# FPGADecoupling.net
KiCad netlist of a schematic drawn in Altium Designer
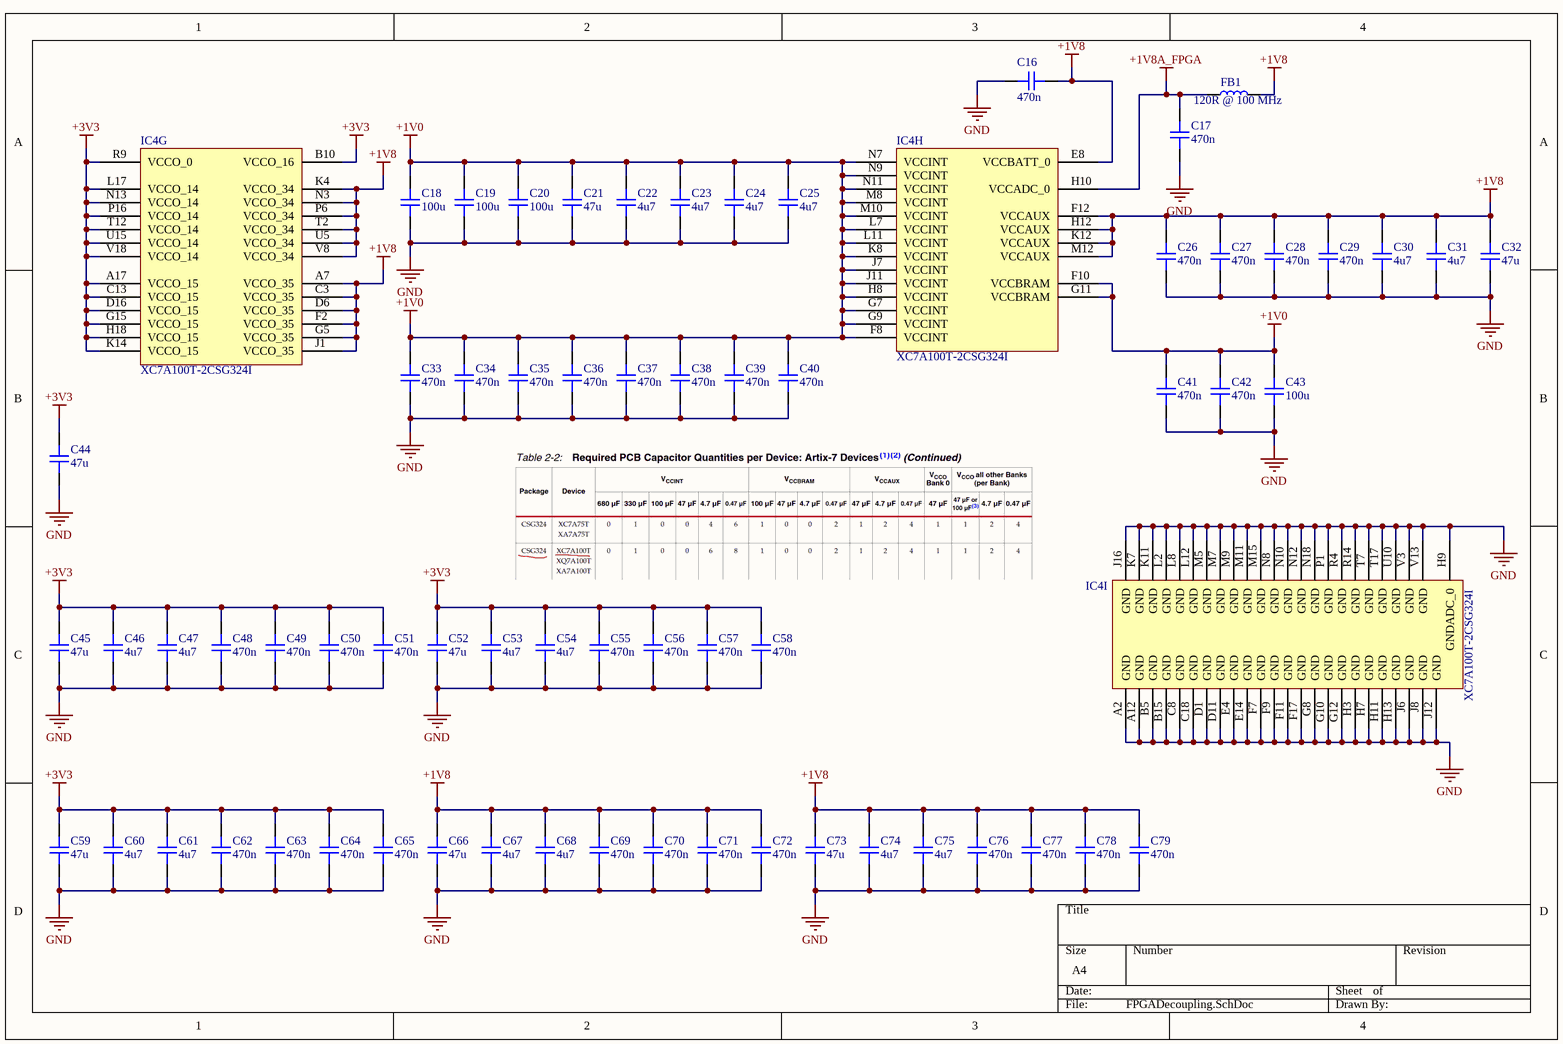
[diagram p0: FPGADecoupling.SchDoc]

(export (version "E")
  (design (tool "Eeschema 10.0.6"))
  (components
    (comp (ref "C16")
      (value "470n")
      (footprint "CAP_0201")
      (description "Capacitor SMD 0201")
      (libsource (lib "Schematic-Lib-PhilsLab") (part "CAP_0201"))
    )
    (comp (ref "C17")
      (value "470n")
      (footprint "CAP_0201")
      (description "Capacitor SMD 0201")
      (libsource (lib "Schematic-Lib-PhilsLab") (part "CAP_0201"))
    )
    (comp (ref "C18")
      (value "100u")
      (footprint "CAP_0805")
      (description "Capacitor SMD 0805")
      (libsource (lib "Schematic-Lib-PhilsLab") (part "CAP_0805"))
    )
    (comp (ref "C19")
      (value "100u")
      (footprint "CAP_0805")
      (description "Capacitor SMD 0805")
      (libsource (lib "Schematic-Lib-PhilsLab") (part "CAP_0805"))
    )
    (comp (ref "C20")
      (value "100u")
      (footprint "CAP_0805")
      (description "Capacitor SMD 0805")
      (libsource (lib "Schematic-Lib-PhilsLab") (part "CAP_0805"))
    )
    (comp (ref "C21")
      (value "47u")
      (footprint "CAP_0603")
      (description "Capacitor SMD 0603")
      (libsource (lib "Schematic-Lib-PhilsLab") (part "CAP_0603"))
    )
    (comp (ref "C22")
      (value "4u7")
      (footprint "CAP_0402")
      (description "Capacitor SMD 0402")
      (libsource (lib "Schematic-Lib-PhilsLab") (part "CAP_0402"))
    )
    (comp (ref "C23")
      (value "4u7")
      (footprint "CAP_0402")
      (description "Capacitor SMD 0402")
      (libsource (lib "Schematic-Lib-PhilsLab") (part "CAP_0402"))
    )
    (comp (ref "C24")
      (value "4u7")
      (footprint "CAP_0402")
      (description "Capacitor SMD 0402")
      (libsource (lib "Schematic-Lib-PhilsLab") (part "CAP_0402"))
    )
    (comp (ref "C25")
      (value "4u7")
      (footprint "CAP_0402")
      (description "Capacitor SMD 0402")
      (libsource (lib "Schematic-Lib-PhilsLab") (part "CAP_0402"))
    )
    (comp (ref "C26")
      (value "470n")
      (footprint "CAP_0201")
      (description "Capacitor SMD 0201")
      (libsource (lib "Schematic-Lib-PhilsLab") (part "CAP_0201"))
    )
    (comp (ref "C27")
      (value "470n")
      (footprint "CAP_0201")
      (description "Capacitor SMD 0201")
      (libsource (lib "Schematic-Lib-PhilsLab") (part "CAP_0201"))
    )
    (comp (ref "C28")
      (value "470n")
      (footprint "CAP_0201")
      (description "Capacitor SMD 0201")
      (libsource (lib "Schematic-Lib-PhilsLab") (part "CAP_0201"))
    )
    (comp (ref "C29")
      (value "470n")
      (footprint "CAP_0201")
      (description "Capacitor SMD 0201")
      (libsource (lib "Schematic-Lib-PhilsLab") (part "CAP_0201"))
    )
    (comp (ref "C30")
      (value "4u7")
      (footprint "CAP_0402")
      (description "Capacitor SMD 0402")
      (libsource (lib "Schematic-Lib-PhilsLab") (part "CAP_0402"))
    )
    (comp (ref "C31")
      (value "4u7")
      (footprint "CAP_0402")
      (description "Capacitor SMD 0402")
      (libsource (lib "Schematic-Lib-PhilsLab") (part "CAP_0402"))
    )
    (comp (ref "C32")
      (value "47u")
      (footprint "CAP_0603")
      (description "Capacitor SMD 0603")
      (libsource (lib "Schematic-Lib-PhilsLab") (part "CAP_0603"))
    )
    (comp (ref "C33")
      (value "470n")
      (footprint "CAP_0201")
      (description "Capacitor SMD 0201")
      (libsource (lib "Schematic-Lib-PhilsLab") (part "CAP_0201"))
    )
    (comp (ref "C34")
      (value "470n")
      (footprint "CAP_0201")
      (description "Capacitor SMD 0201")
      (libsource (lib "Schematic-Lib-PhilsLab") (part "CAP_0201"))
    )
    (comp (ref "C35")
      (value "470n")
      (footprint "CAP_0201")
      (description "Capacitor SMD 0201")
      (libsource (lib "Schematic-Lib-PhilsLab") (part "CAP_0201"))
    )
    (comp (ref "C36")
      (value "470n")
      (footprint "CAP_0201")
      (description "Capacitor SMD 0201")
      (libsource (lib "Schematic-Lib-PhilsLab") (part "CAP_0201"))
    )
    (comp (ref "C37")
      (value "470n")
      (footprint "CAP_0201")
      (description "Capacitor SMD 0201")
      (libsource (lib "Schematic-Lib-PhilsLab") (part "CAP_0201"))
    )
    (comp (ref "C38")
      (value "470n")
      (footprint "CAP_0201")
      (description "Capacitor SMD 0201")
      (libsource (lib "Schematic-Lib-PhilsLab") (part "CAP_0201"))
    )
    (comp (ref "C39")
      (value "470n")
      (footprint "CAP_0201")
      (description "Capacitor SMD 0201")
      (libsource (lib "Schematic-Lib-PhilsLab") (part "CAP_0201"))
    )
    (comp (ref "C40")
      (value "470n")
      (footprint "CAP_0201")
      (description "Capacitor SMD 0201")
      (libsource (lib "Schematic-Lib-PhilsLab") (part "CAP_0201"))
    )
    (comp (ref "C41")
      (value "470n")
      (footprint "CAP_0201")
      (description "Capacitor SMD 0201")
      (libsource (lib "Schematic-Lib-PhilsLab") (part "CAP_0201"))
    )
    (comp (ref "C42")
      (value "470n")
      (footprint "CAP_0201")
      (description "Capacitor SMD 0201")
      (libsource (lib "Schematic-Lib-PhilsLab") (part "CAP_0201"))
    )
    (comp (ref "C43")
      (value "100u")
      (footprint "CAP_0805")
      (description "Capacitor SMD 0805")
      (libsource (lib "Schematic-Lib-PhilsLab") (part "CAP_0805"))
    )
    (comp (ref "C44")
      (value "47u")
      (footprint "CAP_0603")
      (description "Capacitor SMD 0603")
      (libsource (lib "Schematic-Lib-PhilsLab") (part "CAP_0603"))
    )
    (comp (ref "C45")
      (value "47u")
      (footprint "CAP_0603")
      (description "Capacitor SMD 0603")
      (libsource (lib "Schematic-Lib-PhilsLab") (part "CAP_0603"))
    )
    (comp (ref "C46")
      (value "4u7")
      (footprint "CAP_0402")
      (description "Capacitor SMD 0402")
      (libsource (lib "Schematic-Lib-PhilsLab") (part "CAP_0402"))
    )
    (comp (ref "C47")
      (value "4u7")
      (footprint "CAP_0402")
      (description "Capacitor SMD 0402")
      (libsource (lib "Schematic-Lib-PhilsLab") (part "CAP_0402"))
    )
    (comp (ref "C48")
      (value "470n")
      (footprint "CAP_0201")
      (description "Capacitor SMD 0201")
      (libsource (lib "Schematic-Lib-PhilsLab") (part "CAP_0201"))
    )
    (comp (ref "C49")
      (value "470n")
      (footprint "CAP_0201")
      (description "Capacitor SMD 0201")
      (libsource (lib "Schematic-Lib-PhilsLab") (part "CAP_0201"))
    )
    (comp (ref "C50")
      (value "470n")
      (footprint "CAP_0201")
      (description "Capacitor SMD 0201")
      (libsource (lib "Schematic-Lib-PhilsLab") (part "CAP_0201"))
    )
    (comp (ref "C51")
      (value "470n")
      (footprint "CAP_0201")
      (description "Capacitor SMD 0201")
      (libsource (lib "Schematic-Lib-PhilsLab") (part "CAP_0201"))
    )
    (comp (ref "C52")
      (value "47u")
      (footprint "CAP_0603")
      (description "Capacitor SMD 0603")
      (libsource (lib "Schematic-Lib-PhilsLab") (part "CAP_0603"))
    )
    (comp (ref "C53")
      (value "4u7")
      (footprint "CAP_0402")
      (description "Capacitor SMD 0402")
      (libsource (lib "Schematic-Lib-PhilsLab") (part "CAP_0402"))
    )
    (comp (ref "C54")
      (value "4u7")
      (footprint "CAP_0402")
      (description "Capacitor SMD 0402")
      (libsource (lib "Schematic-Lib-PhilsLab") (part "CAP_0402"))
    )
    (comp (ref "C55")
      (value "470n")
      (footprint "CAP_0201")
      (description "Capacitor SMD 0201")
      (libsource (lib "Schematic-Lib-PhilsLab") (part "CAP_0201"))
    )
    (comp (ref "C56")
      (value "470n")
      (footprint "CAP_0201")
      (description "Capacitor SMD 0201")
      (libsource (lib "Schematic-Lib-PhilsLab") (part "CAP_0201"))
    )
    (comp (ref "C57")
      (value "470n")
      (footprint "CAP_0201")
      (description "Capacitor SMD 0201")
      (libsource (lib "Schematic-Lib-PhilsLab") (part "CAP_0201"))
    )
    (comp (ref "C58")
      (value "470n")
      (footprint "CAP_0201")
      (description "Capacitor SMD 0201")
      (libsource (lib "Schematic-Lib-PhilsLab") (part "CAP_0201"))
    )
    (comp (ref "C59")
      (value "47u")
      (footprint "CAP_0603")
      (description "Capacitor SMD 0603")
      (libsource (lib "Schematic-Lib-PhilsLab") (part "CAP_0603"))
    )
    (comp (ref "C60")
      (value "4u7")
      (footprint "CAP_0402")
      (description "Capacitor SMD 0402")
      (libsource (lib "Schematic-Lib-PhilsLab") (part "CAP_0402"))
    )
    (comp (ref "C61")
      (value "4u7")
      (footprint "CAP_0402")
      (description "Capacitor SMD 0402")
      (libsource (lib "Schematic-Lib-PhilsLab") (part "CAP_0402"))
    )
    (comp (ref "C62")
      (value "470n")
      (footprint "CAP_0201")
      (description "Capacitor SMD 0201")
      (libsource (lib "Schematic-Lib-PhilsLab") (part "CAP_0201"))
    )
    (comp (ref "C63")
      (value "470n")
      (footprint "CAP_0201")
      (description "Capacitor SMD 0201")
      (libsource (lib "Schematic-Lib-PhilsLab") (part "CAP_0201"))
    )
    (comp (ref "C64")
      (value "470n")
      (footprint "CAP_0201")
      (description "Capacitor SMD 0201")
      (libsource (lib "Schematic-Lib-PhilsLab") (part "CAP_0201"))
    )
    (comp (ref "C65")
      (value "470n")
      (footprint "CAP_0201")
      (description "Capacitor SMD 0201")
      (libsource (lib "Schematic-Lib-PhilsLab") (part "CAP_0201"))
    )
    (comp (ref "C66")
      (value "47u")
      (footprint "CAP_0603")
      (description "Capacitor SMD 0603")
      (libsource (lib "Schematic-Lib-PhilsLab") (part "CAP_0603"))
    )
    (comp (ref "C67")
      (value "4u7")
      (footprint "CAP_0402")
      (description "Capacitor SMD 0402")
      (libsource (lib "Schematic-Lib-PhilsLab") (part "CAP_0402"))
    )
    (comp (ref "C68")
      (value "4u7")
      (footprint "CAP_0402")
      (description "Capacitor SMD 0402")
      (libsource (lib "Schematic-Lib-PhilsLab") (part "CAP_0402"))
    )
    (comp (ref "C69")
      (value "470n")
      (footprint "CAP_0201")
      (description "Capacitor SMD 0201")
      (libsource (lib "Schematic-Lib-PhilsLab") (part "CAP_0201"))
    )
    (comp (ref "C70")
      (value "470n")
      (footprint "CAP_0201")
      (description "Capacitor SMD 0201")
      (libsource (lib "Schematic-Lib-PhilsLab") (part "CAP_0201"))
    )
    (comp (ref "C71")
      (value "470n")
      (footprint "CAP_0201")
      (description "Capacitor SMD 0201")
      (libsource (lib "Schematic-Lib-PhilsLab") (part "CAP_0201"))
    )
    (comp (ref "C72")
      (value "470n")
      (footprint "CAP_0201")
      (description "Capacitor SMD 0201")
      (libsource (lib "Schematic-Lib-PhilsLab") (part "CAP_0201"))
    )
    (comp (ref "C73")
      (value "47u")
      (footprint "CAP_0603")
      (description "Capacitor SMD 0603")
      (libsource (lib "Schematic-Lib-PhilsLab") (part "CAP_0603"))
    )
    (comp (ref "C74")
      (value "4u7")
      (footprint "CAP_0402")
      (description "Capacitor SMD 0402")
      (libsource (lib "Schematic-Lib-PhilsLab") (part "CAP_0402"))
    )
    (comp (ref "C75")
      (value "4u7")
      (footprint "CAP_0402")
      (description "Capacitor SMD 0402")
      (libsource (lib "Schematic-Lib-PhilsLab") (part "CAP_0402"))
    )
    (comp (ref "C76")
      (value "470n")
      (footprint "CAP_0201")
      (description "Capacitor SMD 0201")
      (libsource (lib "Schematic-Lib-PhilsLab") (part "CAP_0201"))
    )
    (comp (ref "C77")
      (value "470n")
      (footprint "CAP_0201")
      (description "Capacitor SMD 0201")
      (libsource (lib "Schematic-Lib-PhilsLab") (part "CAP_0201"))
    )
    (comp (ref "C78")
      (value "470n")
      (footprint "CAP_0201")
      (description "Capacitor SMD 0201")
      (libsource (lib "Schematic-Lib-PhilsLab") (part "CAP_0201"))
    )
    (comp (ref "C79")
      (value "470n")
      (footprint "CAP_0201")
      (description "Capacitor SMD 0201")
      (libsource (lib "Schematic-Lib-PhilsLab") (part "CAP_0201"))
    )
    (comp (ref "FB1")
      (value "120R @ 100 MHz")
      (footprint "Footprint-Lib-PhilsLab:IND_0201")
      (description "Inductor SMD 0201")
      (fields
        (field (name "MANUFACTURER_PART_NUMBER") "LQP03HQ56NH02D")
        (field (name "MOUSER PART NUMBER") "81-LQP03HQ56NH02D")
      )
      (libsource (lib "Schematic-Lib-PhilsLab") (part "IND_0201"))
    )
    (comp (ref "IC4")
      (value "XC7A100T-2CSG324I")
      (footprint "CSG324")
      (description "Artix-7 FPGA, 210 User I/Os, 0 GTP, 324-Ball BGA, Speed Grade 2, Industrial Grade, Pb-Free")
      (fields (field (name "GENERIC PART NUMBER") "XC7A100T") (field (name "MANUFACTURER") "Xilinx"))
      (libsource (lib "Schematic-Lib-PhilsLab") (part "XC7A100T-2CSG324I"))
    )
  )
  (nets
    (net (code "1") (name "+1V0") (class "Default")
      (node (ref "C18") (pin "2") (pinfunction "2_2") (pintype "passive"))
      (node (ref "C19") (pin "2") (pinfunction "2_2") (pintype "passive"))
      (node (ref "C20") (pin "2") (pinfunction "2_2") (pintype "passive"))
      (node (ref "C21") (pin "2") (pinfunction "2_2") (pintype "passive"))
      (node (ref "C22") (pin "2") (pinfunction "2_2") (pintype "passive"))
      (node (ref "C23") (pin "2") (pinfunction "2_2") (pintype "passive"))
      (node (ref "C24") (pin "2") (pinfunction "2_2") (pintype "passive"))
      (node (ref "C25") (pin "2") (pinfunction "2_2") (pintype "passive"))
      (node (ref "C33") (pin "2") (pinfunction "2_2") (pintype "passive"))
      (node (ref "C34") (pin "2") (pinfunction "2_2") (pintype "passive"))
      (node (ref "C35") (pin "2") (pinfunction "2_2") (pintype "passive"))
      (node (ref "C36") (pin "2") (pinfunction "2_2") (pintype "passive"))
      (node (ref "C37") (pin "2") (pinfunction "2_2") (pintype "passive"))
      (node (ref "C38") (pin "2") (pinfunction "2_2") (pintype "passive"))
      (node (ref "C39") (pin "2") (pinfunction "2_2") (pintype "passive"))
      (node (ref "C40") (pin "2") (pinfunction "2_2") (pintype "passive"))
      (node (ref "C41") (pin "2") (pinfunction "2_2") (pintype "passive"))
      (node (ref "C42") (pin "2") (pinfunction "2_2") (pintype "passive"))
      (node (ref "C43") (pin "2") (pinfunction "2_2") (pintype "passive"))
      (node (ref "IC4") (pin "F10") (pinfunction "VCCBRAM_F10") (pintype "power_in"))
      (node (ref "IC4") (pin "F8") (pinfunction "VCCINT_F8") (pintype "power_in"))
      (node (ref "IC4") (pin "G11") (pinfunction "VCCBRAM_G11") (pintype "power_in"))
      (node (ref "IC4") (pin "G7") (pinfunction "VCCINT_G7") (pintype "power_in"))
      (node (ref "IC4") (pin "G9") (pinfunction "VCCINT_G9") (pintype "power_in"))
      (node (ref "IC4") (pin "H8") (pinfunction "VCCINT_H8") (pintype "power_in"))
      (node (ref "IC4") (pin "J11") (pinfunction "VCCINT_J11") (pintype "power_in"))
      (node (ref "IC4") (pin "J7") (pinfunction "VCCINT_J7") (pintype "power_in"))
      (node (ref "IC4") (pin "K8") (pinfunction "VCCINT_K8") (pintype "power_in"))
      (node (ref "IC4") (pin "L11") (pinfunction "VCCINT_L11") (pintype "power_in"))
      (node (ref "IC4") (pin "L7") (pinfunction "VCCINT_L7") (pintype "power_in"))
      (node (ref "IC4") (pin "M10") (pinfunction "VCCINT_M10") (pintype "power_in"))
      (node (ref "IC4") (pin "M8") (pinfunction "VCCINT_M8") (pintype "power_in"))
      (node (ref "IC4") (pin "N11") (pinfunction "VCCINT_N11") (pintype "power_in"))
      (node (ref "IC4") (pin "N7") (pinfunction "VCCINT_N7") (pintype "power_in"))
      (node (ref "IC4") (pin "N9") (pinfunction "VCCINT_N9") (pintype "power_in"))
    )
    (net (code "2") (name "+1V8") (class "Default")
      (node (ref "C16") (pin "2") (pinfunction "2_2") (pintype "passive"))
      (node (ref "C26") (pin "2") (pinfunction "2_2") (pintype "passive"))
      (node (ref "C27") (pin "2") (pinfunction "2_2") (pintype "passive"))
      (node (ref "C28") (pin "2") (pinfunction "2_2") (pintype "passive"))
      (node (ref "C29") (pin "2") (pinfunction "2_2") (pintype "passive"))
      (node (ref "C30") (pin "2") (pinfunction "2_2") (pintype "passive"))
      (node (ref "C31") (pin "2") (pinfunction "2_2") (pintype "passive"))
      (node (ref "C32") (pin "2") (pinfunction "2_2") (pintype "passive"))
      (node (ref "C66") (pin "2") (pinfunction "2_2") (pintype "passive"))
      (node (ref "C67") (pin "2") (pinfunction "2_2") (pintype "passive"))
      (node (ref "C68") (pin "2") (pinfunction "2_2") (pintype "passive"))
      (node (ref "C69") (pin "2") (pinfunction "2_2") (pintype "passive"))
      (node (ref "C70") (pin "2") (pinfunction "2_2") (pintype "passive"))
      (node (ref "C71") (pin "2") (pinfunction "2_2") (pintype "passive"))
      (node (ref "C72") (pin "2") (pinfunction "2_2") (pintype "passive"))
      (node (ref "C73") (pin "2") (pinfunction "2_2") (pintype "passive"))
      (node (ref "C74") (pin "2") (pinfunction "2_2") (pintype "passive"))
      (node (ref "C75") (pin "2") (pinfunction "2_2") (pintype "passive"))
      (node (ref "C76") (pin "2") (pinfunction "2_2") (pintype "passive"))
      (node (ref "C77") (pin "2") (pinfunction "2_2") (pintype "passive"))
      (node (ref "C78") (pin "2") (pinfunction "2_2") (pintype "passive"))
      (node (ref "C79") (pin "2") (pinfunction "2_2") (pintype "passive"))
      (node (ref "FB1") (pin "2") (pinfunction "2_2") (pintype "passive"))
      (node (ref "IC4") (pin "A7") (pinfunction "VCCO_35_A7") (pintype "power_in"))
      (node (ref "IC4") (pin "C3") (pinfunction "VCCO_35_C3") (pintype "power_in"))
      (node (ref "IC4") (pin "D6") (pinfunction "VCCO_35_D6") (pintype "power_in"))
      (node (ref "IC4") (pin "E8") (pinfunction "VCCBATT_0_E8") (pintype "power_in"))
      (node (ref "IC4") (pin "F12") (pinfunction "VCCAUX_F12") (pintype "power_in"))
      (node (ref "IC4") (pin "F2") (pinfunction "VCCO_35_F2") (pintype "power_in"))
      (node (ref "IC4") (pin "G5") (pinfunction "VCCO_35_G5") (pintype "power_in"))
      (node (ref "IC4") (pin "H12") (pinfunction "VCCAUX_H12") (pintype "power_in"))
      (node (ref "IC4") (pin "J1") (pinfunction "VCCO_35_J1") (pintype "power_in"))
      (node (ref "IC4") (pin "K12") (pinfunction "VCCAUX_K12") (pintype "power_in"))
      (node (ref "IC4") (pin "K4") (pinfunction "VCCO_34_K4") (pintype "power_in"))
      (node (ref "IC4") (pin "M12") (pinfunction "VCCAUX_M12") (pintype "power_in"))
      (node (ref "IC4") (pin "N3") (pinfunction "VCCO_34_N3") (pintype "power_in"))
      (node (ref "IC4") (pin "P6") (pinfunction "VCCO_34_P6") (pintype "power_in"))
      (node (ref "IC4") (pin "T2") (pinfunction "VCCO_34_T2") (pintype "power_in"))
      (node (ref "IC4") (pin "U5") (pinfunction "VCCO_34_U5") (pintype "power_in"))
      (node (ref "IC4") (pin "V8") (pinfunction "VCCO_34_V8") (pintype "power_in"))
    )
    (net (code "3") (name "+1V8A_FPGA") (class "Default")
      (node (ref "C17") (pin "2") (pinfunction "2_2") (pintype "passive"))
      (node (ref "FB1") (pin "1") (pinfunction "1_1") (pintype "passive"))
      (node (ref "IC4") (pin "H10") (pinfunction "VCCADC_0_H10") (pintype "power_in"))
    )
    (net (code "4") (name "+3V3") (class "Default")
      (node (ref "C44") (pin "2") (pinfunction "2_2") (pintype "passive"))
      (node (ref "C45") (pin "2") (pinfunction "2_2") (pintype "passive"))
      (node (ref "C46") (pin "2") (pinfunction "2_2") (pintype "passive"))
      (node (ref "C47") (pin "2") (pinfunction "2_2") (pintype "passive"))
      (node (ref "C48") (pin "2") (pinfunction "2_2") (pintype "passive"))
      (node (ref "C49") (pin "2") (pinfunction "2_2") (pintype "passive"))
      (node (ref "C50") (pin "2") (pinfunction "2_2") (pintype "passive"))
      (node (ref "C51") (pin "2") (pinfunction "2_2") (pintype "passive"))
      (node (ref "C52") (pin "2") (pinfunction "2_2") (pintype "passive"))
      (node (ref "C53") (pin "2") (pinfunction "2_2") (pintype "passive"))
      (node (ref "C54") (pin "2") (pinfunction "2_2") (pintype "passive"))
      (node (ref "C55") (pin "2") (pinfunction "2_2") (pintype "passive"))
      (node (ref "C56") (pin "2") (pinfunction "2_2") (pintype "passive"))
      (node (ref "C57") (pin "2") (pinfunction "2_2") (pintype "passive"))
      (node (ref "C58") (pin "2") (pinfunction "2_2") (pintype "passive"))
      (node (ref "C59") (pin "2") (pinfunction "2_2") (pintype "passive"))
      (node (ref "C60") (pin "2") (pinfunction "2_2") (pintype "passive"))
      (node (ref "C61") (pin "2") (pinfunction "2_2") (pintype "passive"))
      (node (ref "C62") (pin "2") (pinfunction "2_2") (pintype "passive"))
      (node (ref "C63") (pin "2") (pinfunction "2_2") (pintype "passive"))
      (node (ref "C64") (pin "2") (pinfunction "2_2") (pintype "passive"))
      (node (ref "C65") (pin "2") (pinfunction "2_2") (pintype "passive"))
      (node (ref "IC4") (pin "A17") (pinfunction "VCCO_15_A17") (pintype "power_in"))
      (node (ref "IC4") (pin "B10") (pinfunction "VCCO_16_B10") (pintype "power_in"))
      (node (ref "IC4") (pin "C13") (pinfunction "VCCO_15_C13") (pintype "power_in"))
      (node (ref "IC4") (pin "D16") (pinfunction "VCCO_15_D16") (pintype "power_in"))
      (node (ref "IC4") (pin "G15") (pinfunction "VCCO_15_G15") (pintype "power_in"))
      (node (ref "IC4") (pin "H18") (pinfunction "VCCO_15_H18") (pintype "power_in"))
      (node (ref "IC4") (pin "K14") (pinfunction "VCCO_15_K14") (pintype "power_in"))
      (node (ref "IC4") (pin "L17") (pinfunction "VCCO_14_L17") (pintype "power_in"))
      (node (ref "IC4") (pin "N13") (pinfunction "VCCO_14_N13") (pintype "power_in"))
      (node (ref "IC4") (pin "P16") (pinfunction "VCCO_14_P16") (pintype "power_in"))
      (node (ref "IC4") (pin "R9") (pinfunction "VCCO_0_R9") (pintype "power_in"))
      (node (ref "IC4") (pin "T12") (pinfunction "VCCO_14_T12") (pintype "power_in"))
      (node (ref "IC4") (pin "U15") (pinfunction "VCCO_14_U15") (pintype "power_in"))
      (node (ref "IC4") (pin "V18") (pinfunction "VCCO_14_V18") (pintype "power_in"))
    )
    (net (code "5") (name "GND") (class "Default")
      (node (ref "C16") (pin "1") (pinfunction "1_1") (pintype "passive"))
      (node (ref "C17") (pin "1") (pinfunction "1_1") (pintype "passive"))
      (node (ref "C18") (pin "1") (pinfunction "1_1") (pintype "passive"))
      (node (ref "C19") (pin "1") (pinfunction "1_1") (pintype "passive"))
      (node (ref "C20") (pin "1") (pinfunction "1_1") (pintype "passive"))
      (node (ref "C21") (pin "1") (pinfunction "1_1") (pintype "passive"))
      (node (ref "C22") (pin "1") (pinfunction "1_1") (pintype "passive"))
      (node (ref "C23") (pin "1") (pinfunction "1_1") (pintype "passive"))
      (node (ref "C24") (pin "1") (pinfunction "1_1") (pintype "passive"))
      (node (ref "C25") (pin "1") (pinfunction "1_1") (pintype "passive"))
      (node (ref "C26") (pin "1") (pinfunction "1_1") (pintype "passive"))
      (node (ref "C27") (pin "1") (pinfunction "1_1") (pintype "passive"))
      (node (ref "C28") (pin "1") (pinfunction "1_1") (pintype "passive"))
      (node (ref "C29") (pin "1") (pinfunction "1_1") (pintype "passive"))
      (node (ref "C30") (pin "1") (pinfunction "1_1") (pintype "passive"))
      (node (ref "C31") (pin "1") (pinfunction "1_1") (pintype "passive"))
      (node (ref "C32") (pin "1") (pinfunction "1_1") (pintype "passive"))
      (node (ref "C33") (pin "1") (pinfunction "1_1") (pintype "passive"))
      (node (ref "C34") (pin "1") (pinfunction "1_1") (pintype "passive"))
      (node (ref "C35") (pin "1") (pinfunction "1_1") (pintype "passive"))
      (node (ref "C36") (pin "1") (pinfunction "1_1") (pintype "passive"))
      (node (ref "C37") (pin "1") (pinfunction "1_1") (pintype "passive"))
      (node (ref "C38") (pin "1") (pinfunction "1_1") (pintype "passive"))
      (node (ref "C39") (pin "1") (pinfunction "1_1") (pintype "passive"))
      (node (ref "C40") (pin "1") (pinfunction "1_1") (pintype "passive"))
      (node (ref "C41") (pin "1") (pinfunction "1_1") (pintype "passive"))
      (node (ref "C42") (pin "1") (pinfunction "1_1") (pintype "passive"))
      (node (ref "C43") (pin "1") (pinfunction "1_1") (pintype "passive"))
      (node (ref "C44") (pin "1") (pinfunction "1_1") (pintype "passive"))
      (node (ref "C45") (pin "1") (pinfunction "1_1") (pintype "passive"))
      (node (ref "C46") (pin "1") (pinfunction "1_1") (pintype "passive"))
      (node (ref "C47") (pin "1") (pinfunction "1_1") (pintype "passive"))
      (node (ref "C48") (pin "1") (pinfunction "1_1") (pintype "passive"))
      (node (ref "C49") (pin "1") (pinfunction "1_1") (pintype "passive"))
      (node (ref "C50") (pin "1") (pinfunction "1_1") (pintype "passive"))
      (node (ref "C51") (pin "1") (pinfunction "1_1") (pintype "passive"))
      (node (ref "C52") (pin "1") (pinfunction "1_1") (pintype "passive"))
      (node (ref "C53") (pin "1") (pinfunction "1_1") (pintype "passive"))
      (node (ref "C54") (pin "1") (pinfunction "1_1") (pintype "passive"))
      (node (ref "C55") (pin "1") (pinfunction "1_1") (pintype "passive"))
      (node (ref "C56") (pin "1") (pinfunction "1_1") (pintype "passive"))
      (node (ref "C57") (pin "1") (pinfunction "1_1") (pintype "passive"))
      (node (ref "C58") (pin "1") (pinfunction "1_1") (pintype "passive"))
      (node (ref "C59") (pin "1") (pinfunction "1_1") (pintype "passive"))
      (node (ref "C60") (pin "1") (pinfunction "1_1") (pintype "passive"))
      (node (ref "C61") (pin "1") (pinfunction "1_1") (pintype "passive"))
      (node (ref "C62") (pin "1") (pinfunction "1_1") (pintype "passive"))
      (node (ref "C63") (pin "1") (pinfunction "1_1") (pintype "passive"))
      (node (ref "C64") (pin "1") (pinfunction "1_1") (pintype "passive"))
      (node (ref "C65") (pin "1") (pinfunction "1_1") (pintype "passive"))
      (node (ref "C66") (pin "1") (pinfunction "1_1") (pintype "passive"))
      (node (ref "C67") (pin "1") (pinfunction "1_1") (pintype "passive"))
      (node (ref "C68") (pin "1") (pinfunction "1_1") (pintype "passive"))
      (node (ref "C69") (pin "1") (pinfunction "1_1") (pintype "passive"))
      (node (ref "C70") (pin "1") (pinfunction "1_1") (pintype "passive"))
      (node (ref "C71") (pin "1") (pinfunction "1_1") (pintype "passive"))
      (node (ref "C72") (pin "1") (pinfunction "1_1") (pintype "passive"))
      (node (ref "C73") (pin "1") (pinfunction "1_1") (pintype "passive"))
      (node (ref "C74") (pin "1") (pinfunction "1_1") (pintype "passive"))
      (node (ref "C75") (pin "1") (pinfunction "1_1") (pintype "passive"))
      (node (ref "C76") (pin "1") (pinfunction "1_1") (pintype "passive"))
      (node (ref "C77") (pin "1") (pinfunction "1_1") (pintype "passive"))
      (node (ref "C78") (pin "1") (pinfunction "1_1") (pintype "passive"))
      (node (ref "C79") (pin "1") (pinfunction "1_1") (pintype "passive"))
      (node (ref "IC4") (pin "A12") (pinfunction "GND_A12") (pintype "power_in"))
      (node (ref "IC4") (pin "A2") (pinfunction "GND_A2") (pintype "power_in"))
      (node (ref "IC4") (pin "B15") (pinfunction "GND_B15") (pintype "power_in"))
      (node (ref "IC4") (pin "B5") (pinfunction "GND_B5") (pintype "power_in"))
      (node (ref "IC4") (pin "C18") (pinfunction "GND_C18") (pintype "power_in"))
      (node (ref "IC4") (pin "C8") (pinfunction "GND_C8") (pintype "power_in"))
      (node (ref "IC4") (pin "D1") (pinfunction "GND_D1") (pintype "power_in"))
      (node (ref "IC4") (pin "D11") (pinfunction "GND_D11") (pintype "power_in"))
      (node (ref "IC4") (pin "E14") (pinfunction "GND_E14") (pintype "power_in"))
      (node (ref "IC4") (pin "E4") (pinfunction "GND_E4") (pintype "power_in"))
      (node (ref "IC4") (pin "F11") (pinfunction "GND_F11") (pintype "power_in"))
      (node (ref "IC4") (pin "F17") (pinfunction "GND_F17") (pintype "power_in"))
      (node (ref "IC4") (pin "F7") (pinfunction "GND_F7") (pintype "power_in"))
      (node (ref "IC4") (pin "F9") (pinfunction "GND_F9") (pintype "power_in"))
      (node (ref "IC4") (pin "G10") (pinfunction "GND_G10") (pintype "power_in"))
      (node (ref "IC4") (pin "G12") (pinfunction "GND_G12") (pintype "power_in"))
      (node (ref "IC4") (pin "G8") (pinfunction "GND_G8") (pintype "power_in"))
      (node (ref "IC4") (pin "H11") (pinfunction "GND_H11") (pintype "power_in"))
      (node (ref "IC4") (pin "H13") (pinfunction "GND_H13") (pintype "power_in"))
      (node (ref "IC4") (pin "H3") (pinfunction "GND_H3") (pintype "power_in"))
      (node (ref "IC4") (pin "H7") (pinfunction "GND_H7") (pintype "power_in"))
      (node (ref "IC4") (pin "H9") (pinfunction "GNDADC_0_H9") (pintype "power_in"))
      (node (ref "IC4") (pin "J12") (pinfunction "GND_J12") (pintype "power_in"))
      (node (ref "IC4") (pin "J16") (pinfunction "GND_J16") (pintype "power_in"))
      (node (ref "IC4") (pin "J6") (pinfunction "GND_J6") (pintype "power_in"))
      (node (ref "IC4") (pin "J8") (pinfunction "GND_J8") (pintype "power_in"))
      (node (ref "IC4") (pin "K11") (pinfunction "GND_K11") (pintype "power_in"))
      (node (ref "IC4") (pin "K7") (pinfunction "GND_K7") (pintype "power_in"))
      (node (ref "IC4") (pin "L12") (pinfunction "GND_L12") (pintype "power_in"))
      (node (ref "IC4") (pin "L2") (pinfunction "GND_L2") (pintype "power_in"))
      (node (ref "IC4") (pin "L8") (pinfunction "GND_L8") (pintype "power_in"))
      (node (ref "IC4") (pin "M11") (pinfunction "GND_M11") (pintype "power_in"))
      (node (ref "IC4") (pin "M15") (pinfunction "GND_M15") (pintype "power_in"))
      (node (ref "IC4") (pin "M5") (pinfunction "GND_M5") (pintype "power_in"))
      (node (ref "IC4") (pin "M7") (pinfunction "GND_M7") (pintype "power_in"))
      (node (ref "IC4") (pin "M9") (pinfunction "GND_M9") (pintype "power_in"))
      (node (ref "IC4") (pin "N10") (pinfunction "GND_N10") (pintype "power_in"))
      (node (ref "IC4") (pin "N12") (pinfunction "GND_N12") (pintype "power_in"))
      (node (ref "IC4") (pin "N18") (pinfunction "GND_N18") (pintype "power_in"))
      (node (ref "IC4") (pin "N8") (pinfunction "GND_N8") (pintype "power_in"))
      (node (ref "IC4") (pin "P1") (pinfunction "GND_P1") (pintype "power_in"))
      (node (ref "IC4") (pin "R14") (pinfunction "GND_R14") (pintype "power_in"))
      (node (ref "IC4") (pin "R4") (pinfunction "GND_R4") (pintype "power_in"))
      (node (ref "IC4") (pin "T17") (pinfunction "GND_T17") (pintype "power_in"))
      (node (ref "IC4") (pin "T7") (pinfunction "GND_T7") (pintype "power_in"))
      (node (ref "IC4") (pin "U10") (pinfunction "GND_U10") (pintype "power_in"))
      (node (ref "IC4") (pin "V13") (pinfunction "GND_V13") (pintype "power_in"))
      (node (ref "IC4") (pin "V3") (pinfunction "GND_V3") (pintype "power_in"))
    )
  )
)
